# usb_uart.net
KiCad netlist of a schematic drawn in Altium Designer
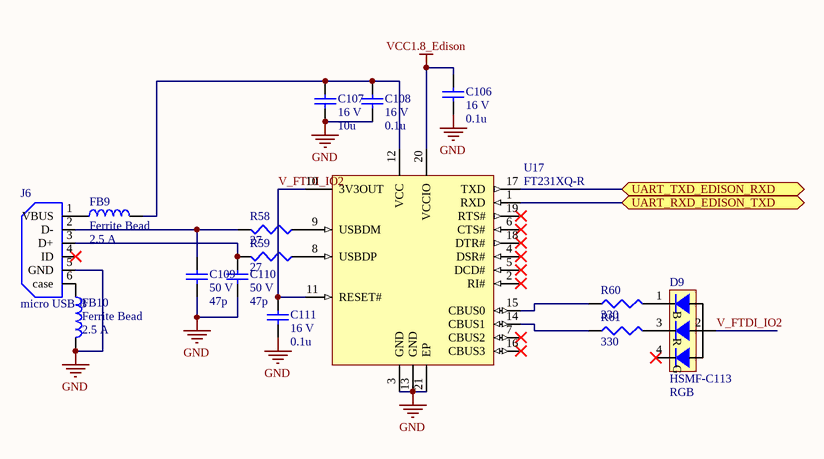
[diagram p0: usb_uart.SchDoc]

(export (version "E")
  (design (tool "Eeschema 10.0.6"))
  (components
    (comp (ref "C106")
      (value "0.1u")
      (footprint "0402")
      (description "0.10µF ±10% 16V Ceramic Capacitor X7R 0402")
      (fields
        (field (name "TOLERANCE") "10%")
        (field (name "VOLTAGE RATED") "16 V")
        (field (name "MANUFACTURER PART NUMBER") "GRM155R71C104KA88D")
      )
      (libsource (lib "capacitors") (part "GRM155R71C104KA88D"))
    )
    (comp (ref "C107")
      (value "10u")
      (footprint "0603")
      (description "10µF ±20% 16V Ceramic Capacitor X6S 0603")
      (fields
        (field (name "TOLERANCE") "20%")
        (field (name "VOLTAGE RATED") "16 V")
        (field (name "MANUFACTURER PART NUMBER") "GRM188C81C106MA73D")
      )
      (libsource (lib "capacitors") (part "GRM188C81C106MA73D"))
    )
    (comp (ref "C108")
      (value "0.1u")
      (footprint "0402")
      (description "0.10µF ±10% 16V Ceramic Capacitor X7R 0402")
      (fields
        (field (name "TOLERANCE") "10%")
        (field (name "VOLTAGE RATED") "16 V")
        (field (name "MANUFACTURER PART NUMBER") "GRM155R71C104KA88D")
      )
      (libsource (lib "capacitors") (part "GRM155R71C104KA88D"))
    )
    (comp (ref "C109")
      (value "47p")
      (footprint "0402")
      (description "47pF ±5% 50V Ceramic Capacitor C0G, NP0 0402")
      (fields
        (field (name "TOLERANCE") "5%")
        (field (name "VOLTAGE RATED") "50 V")
        (field (name "MANUFACTURER PART NUMBER") "500R07N470JV4T")
      )
      (libsource (lib "capacitors") (part "500R07N470JV4T"))
    )
    (comp (ref "C110")
      (value "47p")
      (footprint "0402")
      (description "47pF ±5% 50V Ceramic Capacitor C0G, NP0 0402")
      (fields
        (field (name "TOLERANCE") "5%")
        (field (name "VOLTAGE RATED") "50 V")
        (field (name "MANUFACTURER PART NUMBER") "500R07N470JV4T")
      )
      (libsource (lib "capacitors") (part "500R07N470JV4T"))
    )
    (comp (ref "C111")
      (value "0.1u")
      (footprint "0402")
      (description "0.10µF ±10% 16V Ceramic Capacitor X7R 0402")
      (fields
        (field (name "TOLERANCE") "10%")
        (field (name "VOLTAGE RATED") "16 V")
        (field (name "MANUFACTURER PART NUMBER") "GRM155R71C104KA88D")
      )
      (libsource (lib "capacitors") (part "GRM155R71C104KA88D"))
    )
    (comp (ref "D9")
      (value "HSMF-C113")
      (footprint "HSMF")
      (fields (field (name "MANUFACTURER") "Broadcom Limited") (field (name "ALTIUM_VALUE") "RGB"))
      (libsource (lib "LED") (part "HSMF-C113"))
    )
    (comp (ref "FB9")
      (value "Ferrite Bead")
      (footprint "0603")
      (description "FERRITE BEAD 220 OHM 0603")
      (fields
        (field (name "MANUFACTURER PART NUMBER") "BLM18SG221TN1D")
        (field (name "MANUFACTURER") "Murata")
        (field (name "CURRENT RATING (MAX)") "2.5 A")
      )
      (libsource (lib "ferrite_beads") (part "BLM18SG221TN1D"))
    )
    (comp (ref "FB10")
      (value "Ferrite Bead")
      (footprint "0603")
      (description "FERRITE BEAD 220 OHM 0603")
      (fields
        (field (name "MANUFACTURER PART NUMBER") "BLM18SG221TN1D")
        (field (name "MANUFACTURER") "Murata")
        (field (name "CURRENT RATING (MAX)") "2.5 A")
      )
      (libsource (lib "") (part "BLM18SG221TN1D_1"))
    )
    (comp (ref "J6")
      (value "micro USB-B")
      (footprint "Micro USB-B")
      (description "CONN USB MICRO B RECPT SMT R/A")
      (libsource (lib "connectors") (part "Micro USB"))
    )
    (comp (ref "R58")
      (value "27")
      (footprint "0402")
      (description "RES SMD 27 OHM 1% 1/16W 0402")
      (fields (field (name "TOLERANCE") "1%") (field (name "POWER") "1/16 W"))
      (libsource (lib "resistors") (part "CRCW040227R0FKED"))
    )
    (comp (ref "R59")
      (value "27")
      (footprint "0402")
      (description "RES SMD 27 OHM 1% 1/16W 0402")
      (fields (field (name "TOLERANCE") "1%") (field (name "POWER") "1/16 W"))
      (libsource (lib "resistors") (part "CRCW040227R0FKED"))
    )
    (comp (ref "R60")
      (value "330")
      (footprint "0402")
      (description "RES SMD 330 OHM 1% 1/16W 0402")
      (fields (field (name "TOLERANCE") "1%") (field (name "POWER") "1/16 W"))
      (libsource (lib "resistors") (part "CRCW0402330RFKED"))
    )
    (comp (ref "R61")
      (value "330")
      (footprint "0402")
      (description "RES SMD 330 OHM 1% 1/16W 0402")
      (fields (field (name "TOLERANCE") "1%") (field (name "POWER") "1/16 W"))
      (libsource (lib "resistors") (part "CRCW0402330RFKED"))
    )
    (comp (ref "U17")
      (value "FT231XQ-R")
      (footprint "QFN-20_N")
      (fields (field (name "MANUFACTURER") "FTDI"))
      (libsource (lib "FTDI FT-X Series") (part "FT231XQ-R"))
    )
  )
  (nets
    (net (code "1") (name "/UART_RXD_EDISON_TXD") (class "Default")
      (node (ref "U17") (pin "1") (pinfunction "RXD_1") (pintype "input"))
    )
    (net (code "2") (name "/UART_TXD_EDISON_RXD") (class "Default")
      (node (ref "U17") (pin "17") (pinfunction "TXD_17") (pintype "output"))
    )
    (net (code "3") (name "/V_FTDI_IO2") (class "Default")
      (node (ref "C111") (pin "1") (pintype "passive"))
      (node (ref "D9") (pin "2") (pintype "passive"))
      (node (ref "U17") (pin "10") (pinfunction "3V3OUT_10") (pintype "power_in"))
      (node (ref "U17") (pin "11") (pinfunction "RESET#_11") (pintype "input"))
    )
    (net (code "4") (name "GND") (class "Default")
      (node (ref "C106") (pin "2") (pintype "passive"))
      (node (ref "C107") (pin "2") (pintype "passive"))
      (node (ref "C108") (pin "2") (pintype "passive"))
      (node (ref "C109") (pin "2") (pintype "passive"))
      (node (ref "C110") (pin "2") (pintype "passive"))
      (node (ref "C111") (pin "2") (pintype "passive"))
      (node (ref "FB10") (pin "1") (pintype "passive"))
      (node (ref "J6") (pin "5") (pinfunction "GND_5") (pintype "power_in"))
      (node (ref "U17") (pin "13") (pinfunction "GND_13") (pintype "power_in"))
      (node (ref "U17") (pin "21") (pinfunction "EP_21") (pintype "power_in"))
      (node (ref "U17") (pin "3") (pinfunction "GND_3") (pintype "power_in"))
    )
    (net (code "5") (name "Net-(D9-Pad1)") (class "Default")
      (node (ref "D9") (pin "1") (pintype "passive"))
      (node (ref "R60") (pin "1") (pintype "passive"))
    )
    (net (code "6") (name "Net-(D9-Pad3)") (class "Default")
      (node (ref "D9") (pin "3") (pinfunction "3_3") (pintype "passive"))
      (node (ref "R61") (pin "1") (pintype "passive"))
    )
    (net (code "7") (name "Net-(J6-D+)") (class "Default")
      (node (ref "C110") (pin "1") (pintype "passive"))
      (node (ref "J6") (pin "3") (pinfunction "D+_3") (pintype "power_in"))
      (node (ref "R59") (pin "1") (pintype "passive"))
    )
    (net (code "8") (name "Net-(J6-D-)") (class "Default")
      (node (ref "C109") (pin "1") (pintype "passive"))
      (node (ref "J6") (pin "2") (pinfunction "D-_2") (pintype "power_in"))
      (node (ref "R58") (pin "1") (pintype "passive"))
    )
    (net (code "9") (name "Net-(J6-VBUS)") (class "Default")
      (node (ref "FB9") (pin "2") (pintype "passive"))
      (node (ref "J6") (pin "1") (pinfunction "VBUS_1") (pintype "power_in"))
    )
    (net (code "10") (name "Net-(J6-case)") (class "Default")
      (node (ref "FB10") (pin "2") (pintype "passive"))
      (node (ref "J6") (pin "6") (pinfunction "case_6") (pintype "power_in"))
    )
    (net (code "11") (name "Net-(U17-CBUS0)") (class "Default")
      (node (ref "R60") (pin "2") (pintype "passive"))
      (node (ref "U17") (pin "15") (pinfunction "CBUS0_15") (pintype "bidirectional"))
    )
    (net (code "12") (name "Net-(U17-CBUS1)") (class "Default")
      (node (ref "R61") (pin "2") (pintype "passive"))
      (node (ref "U17") (pin "14") (pinfunction "CBUS1_14") (pintype "bidirectional"))
    )
    (net (code "13") (name "Net-(U17-USBDM)") (class "Default")
      (node (ref "R58") (pin "2") (pintype "passive"))
      (node (ref "U17") (pin "9") (pinfunction "USBDM_9") (pintype "input"))
    )
    (net (code "14") (name "Net-(U17-USBDP)") (class "Default")
      (node (ref "R59") (pin "2") (pintype "passive"))
      (node (ref "U17") (pin "8") (pinfunction "USBDP_8") (pintype "input"))
    )
    (net (code "15") (name "Net-(U17-VCC)") (class "Default")
      (node (ref "C107") (pin "1") (pintype "passive"))
      (node (ref "C108") (pin "1") (pintype "passive"))
      (node (ref "FB9") (pin "1") (pintype "passive"))
      (node (ref "U17") (pin "12") (pinfunction "VCC_12") (pintype "power_in"))
    )
    (net (code "16") (name "VCC1.8_Edison") (class "Default")
      (node (ref "C106") (pin "1") (pintype "passive"))
      (node (ref "U17") (pin "20") (pinfunction "VCCIO_20") (pintype "power_in"))
    )
    (net (code "17") (name "unconnected-(D9-Pad4)") (class "Default")
      (node (ref "D9") (pin "4") (pinfunction "4_4") (pintype "passive+no_connect"))
    )
    (net (code "18") (name "unconnected-(J6-ID-Pad4)") (class "Default")
      (node (ref "J6") (pin "4") (pinfunction "ID_4") (pintype "power_in+no_connect"))
    )
    (net (code "19") (name "unconnected-(U17-CBUS2-Pad7)") (class "Default")
      (node (ref "U17") (pin "7") (pinfunction "CBUS2_7") (pintype "bidirectional+no_connect"))
    )
    (net (code "20") (name "unconnected-(U17-CBUS3-Pad16)") (class "Default")
      (node (ref "U17") (pin "16") (pinfunction "CBUS3_16") (pintype "bidirectional+no_connect"))
    )
    (net (code "21") (name "unconnected-(U17-CTS#-Pad6)") (class "Default")
      (node (ref "U17") (pin "6") (pinfunction "CTS#_6") (pintype "input+no_connect"))
    )
    (net (code "22") (name "unconnected-(U17-DCD#-Pad5)") (class "Default")
      (node (ref "U17") (pin "5") (pinfunction "DCD#_5") (pintype "input+no_connect"))
    )
    (net (code "23") (name "unconnected-(U17-DSR#-Pad4)") (class "Default")
      (node (ref "U17") (pin "4") (pinfunction "DSR#_4") (pintype "input+no_connect"))
    )
    (net (code "24") (name "unconnected-(U17-DTR#-Pad18)") (class "Default")
      (node (ref "U17") (pin "18") (pinfunction "DTR#_18") (pintype "output+no_connect"))
    )
    (net (code "25") (name "unconnected-(U17-RI#-Pad2)") (class "Default")
      (node (ref "U17") (pin "2") (pinfunction "RI#_2") (pintype "input+no_connect"))
    )
    (net (code "26") (name "unconnected-(U17-RTS#-Pad19)") (class "Default")
      (node (ref "U17") (pin "19") (pinfunction "RTS#_19") (pintype "output+no_connect"))
    )
  )
)
